# ESP12-breakout-pth-rev1.net
KiCad netlist of a schematic drawn in EAGLE
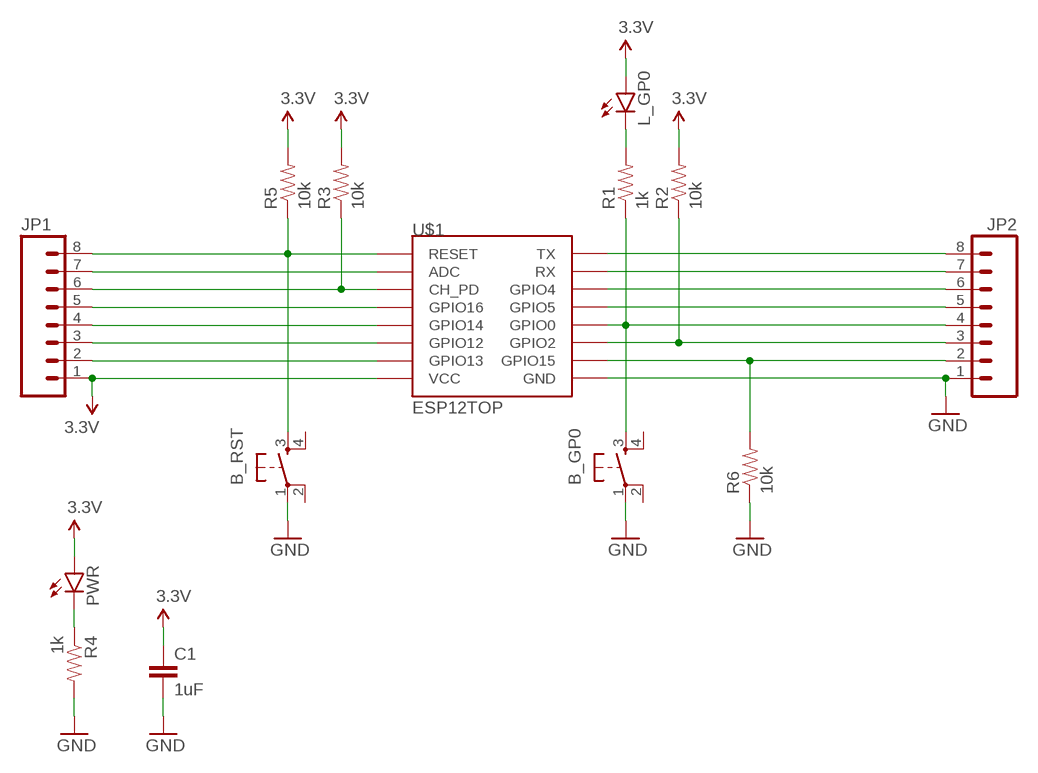
[diagram p0: schematic, sheet 1]

(export (version "E")
  (design (tool "Eeschema 10.0.6"))
  (components
    (comp (ref "B_GP0")
      (value "TAC_SWITCHPTH")
      (footprint "eagle-import:TACTILE-PTH")
      (libsource (lib "eagle-import") (part "TAC_SWITCHPTH"))
    )
    (comp (ref "B_RST")
      (value "TAC_SWITCHPTH")
      (footprint "eagle-import:TACTILE-PTH")
      (libsource (lib "eagle-import") (part "TAC_SWITCHPTH"))
    )
    (comp (ref "C1")
      (value "1uF")
      (footprint "eagle-import:CAP-PTH-SMALL")
      (libsource (lib "eagle-import") (part "CAPPTH"))
    )
    (comp (ref "JP1")
      (value "M08")
      (footprint "eagle-import:1X08_PIN1_NO_SILK")
      (libsource (lib "eagle-import") (part "M08"))
    )
    (comp (ref "JP2")
      (value "M08")
      (footprint "eagle-import:1X08_PIN1_NO_SILK")
      (libsource (lib "eagle-import") (part "M08"))
    )
    (comp (ref "L_GP0")
      (value "LED3MM")
      (footprint "eagle-import:LED3MM")
      (libsource (lib "eagle-import") (part "LED3MM"))
    )
    (comp (ref "PWR")
      (value "LED3MM")
      (footprint "eagle-import:LED3MM")
      (libsource (lib "eagle-import") (part "LED3MM"))
    )
    (comp (ref "R1")
      (value "1k")
      (footprint "eagle-import:1_6W-RES")
      (libsource (lib "eagle-import") (part "RESISTORPTH-1/6W"))
    )
    (comp (ref "R2")
      (value "10k")
      (footprint "eagle-import:1_6W-RES")
      (libsource (lib "eagle-import") (part "RESISTORPTH-1/6W"))
    )
    (comp (ref "R3")
      (value "10k")
      (footprint "eagle-import:1_6W-RES")
      (libsource (lib "eagle-import") (part "RESISTORPTH-1/6W"))
    )
    (comp (ref "R4")
      (value "1k")
      (footprint "eagle-import:1_6W-RES")
      (libsource (lib "eagle-import") (part "RESISTORPTH-1/6W"))
    )
    (comp (ref "R5")
      (value "10k")
      (footprint "eagle-import:1_6W-RES")
      (libsource (lib "eagle-import") (part "RESISTORPTH-1/6W"))
    )
    (comp (ref "R6")
      (value "10k")
      (footprint "eagle-import:1_6W-RES")
      (libsource (lib "eagle-import") (part "RESISTORPTH-1/6W"))
    )
    (comp (ref "U$1")
      (value "ESP12TOP")
      (footprint "eagle-import:ESP12TOP")
      (libsource (lib "eagle-import") (part "ESP12TOP"))
    )
  )
  (nets
    (net (code "1") (name "3.3V") (class "Default")
      (node (ref "C1") (pin "1") (pinfunction "1_1") (pintype "passive"))
      (node (ref "JP1") (pin "1") (pinfunction "1_1") (pintype "passive"))
      (node (ref "L_GP0") (pin "A") (pinfunction "A_A") (pintype "passive"))
      (node (ref "PWR") (pin "A") (pinfunction "A_A") (pintype "passive"))
      (node (ref "R2") (pin "2") (pinfunction "2_2") (pintype "passive"))
      (node (ref "R3") (pin "2") (pinfunction "2_2") (pintype "passive"))
      (node (ref "R5") (pin "2") (pinfunction "2_2") (pintype "passive"))
      (node (ref "U$1") (pin "VCC") (pinfunction "VCC_VCC") (pintype "bidirectional"))
    )
    (net (code "2") (name "GND") (class "Default")
      (node (ref "B_GP0") (pin "1") (pinfunction "1_1") (pintype "passive"))
      (node (ref "B_RST") (pin "1") (pinfunction "1_1") (pintype "passive"))
      (node (ref "C1") (pin "2") (pinfunction "2_2") (pintype "passive"))
      (node (ref "JP2") (pin "1") (pinfunction "1_1") (pintype "passive"))
      (node (ref "R4") (pin "2") (pinfunction "2_2") (pintype "passive"))
      (node (ref "R6") (pin "1") (pinfunction "1_1") (pintype "passive"))
      (node (ref "U$1") (pin "GND") (pinfunction "GND_GND") (pintype "bidirectional"))
    )
    (net (code "3") (name "Net-(B_GP0-Pad3)") (class "Default")
      (node (ref "B_GP0") (pin "3") (pinfunction "3_3") (pintype "passive"))
      (node (ref "JP2") (pin "4") (pinfunction "4_4") (pintype "passive"))
      (node (ref "R1") (pin "1") (pinfunction "1_1") (pintype "passive"))
      (node (ref "U$1") (pin "GPIO0") (pinfunction "GPIO0_GPIO0") (pintype "bidirectional"))
    )
    (net (code "4") (name "Net-(B_RST-Pad3)") (class "Default")
      (node (ref "B_RST") (pin "3") (pinfunction "3_3") (pintype "passive"))
      (node (ref "JP1") (pin "8") (pinfunction "8_8") (pintype "passive"))
      (node (ref "R5") (pin "1") (pinfunction "1_1") (pintype "passive"))
      (node (ref "U$1") (pin "RESET") (pinfunction "RESET_RESET") (pintype "bidirectional"))
    )
    (net (code "5") (name "Net-(JP1-Pad2)") (class "Default")
      (node (ref "JP1") (pin "2") (pinfunction "2_2") (pintype "passive"))
      (node (ref "U$1") (pin "GPIO13") (pinfunction "GPIO13_GPIO13") (pintype "bidirectional"))
    )
    (net (code "6") (name "Net-(JP1-Pad3)") (class "Default")
      (node (ref "JP1") (pin "3") (pinfunction "3_3") (pintype "passive"))
      (node (ref "U$1") (pin "GPIO12") (pinfunction "GPIO12_GPIO12") (pintype "bidirectional"))
    )
    (net (code "7") (name "Net-(JP1-Pad4)") (class "Default")
      (node (ref "JP1") (pin "4") (pinfunction "4_4") (pintype "passive"))
      (node (ref "U$1") (pin "GPIO14") (pinfunction "GPIO14_GPIO14") (pintype "bidirectional"))
    )
    (net (code "8") (name "Net-(JP1-Pad5)") (class "Default")
      (node (ref "JP1") (pin "5") (pinfunction "5_5") (pintype "passive"))
      (node (ref "U$1") (pin "GPIO16") (pinfunction "GPIO16_GPIO16") (pintype "bidirectional"))
    )
    (net (code "9") (name "Net-(JP1-Pad6)") (class "Default")
      (node (ref "JP1") (pin "6") (pinfunction "6_6") (pintype "passive"))
      (node (ref "R3") (pin "1") (pinfunction "1_1") (pintype "passive"))
      (node (ref "U$1") (pin "CH_PD") (pinfunction "CH_PD_CH_PD") (pintype "bidirectional"))
    )
    (net (code "10") (name "Net-(JP1-Pad7)") (class "Default")
      (node (ref "JP1") (pin "7") (pinfunction "7_7") (pintype "passive"))
      (node (ref "U$1") (pin "ADC") (pinfunction "ADC_ADC") (pintype "bidirectional"))
    )
    (net (code "11") (name "Net-(JP2-Pad2)") (class "Default")
      (node (ref "JP2") (pin "2") (pinfunction "2_2") (pintype "passive"))
      (node (ref "R6") (pin "2") (pinfunction "2_2") (pintype "passive"))
      (node (ref "U$1") (pin "GPIO15") (pinfunction "GPIO15_GPIO15") (pintype "bidirectional"))
    )
    (net (code "12") (name "Net-(JP2-Pad3)") (class "Default")
      (node (ref "JP2") (pin "3") (pinfunction "3_3") (pintype "passive"))
      (node (ref "R2") (pin "1") (pinfunction "1_1") (pintype "passive"))
      (node (ref "U$1") (pin "GPIO2") (pinfunction "GPIO2_GPIO2") (pintype "bidirectional"))
    )
    (net (code "13") (name "Net-(JP2-Pad5)") (class "Default")
      (node (ref "JP2") (pin "5") (pinfunction "5_5") (pintype "passive"))
      (node (ref "U$1") (pin "GPIO5") (pinfunction "GPIO5_GPIO5") (pintype "bidirectional"))
    )
    (net (code "14") (name "Net-(JP2-Pad6)") (class "Default")
      (node (ref "JP2") (pin "6") (pinfunction "6_6") (pintype "passive"))
      (node (ref "U$1") (pin "GPIO4") (pinfunction "GPIO4_GPIO4") (pintype "bidirectional"))
    )
    (net (code "15") (name "Net-(L_GP0-C)") (class "Default")
      (node (ref "L_GP0") (pin "K") (pinfunction "C_K") (pintype "passive"))
      (node (ref "R1") (pin "2") (pinfunction "2_2") (pintype "passive"))
    )
    (net (code "16") (name "Net-(PWR-C)") (class "Default")
      (node (ref "PWR") (pin "K") (pinfunction "C_K") (pintype "passive"))
      (node (ref "R4") (pin "1") (pinfunction "1_1") (pintype "passive"))
    )
    (net (code "17") (name "Net-(U$1-RX)") (class "Default")
      (node (ref "JP2") (pin "7") (pinfunction "7_7") (pintype "passive"))
      (node (ref "U$1") (pin "RXD") (pinfunction "RX_RXD") (pintype "bidirectional"))
    )
    (net (code "18") (name "Net-(U$1-TX)") (class "Default")
      (node (ref "JP2") (pin "8") (pinfunction "8_8") (pintype "passive"))
      (node (ref "U$1") (pin "TXD") (pinfunction "TX_TXD") (pintype "bidirectional"))
    )
    (net (code "19") (name "unconnected-(B_GP0-Pad2)") (class "Default")
      (node (ref "B_GP0") (pin "2") (pinfunction "2_2") (pintype "passive"))
    )
    (net (code "20") (name "unconnected-(B_GP0-Pad4)") (class "Default")
      (node (ref "B_GP0") (pin "4") (pinfunction "4_4") (pintype "passive"))
    )
    (net (code "21") (name "unconnected-(B_RST-Pad2)") (class "Default")
      (node (ref "B_RST") (pin "2") (pinfunction "2_2") (pintype "passive"))
    )
    (net (code "22") (name "unconnected-(B_RST-Pad4)") (class "Default")
      (node (ref "B_RST") (pin "4") (pinfunction "4_4") (pintype "passive"))
    )
  )
)
